# PIR_Sensor_driver_v5_1-Cheburan.net
KiCad netlist of a schematic drawn in Altium Designer
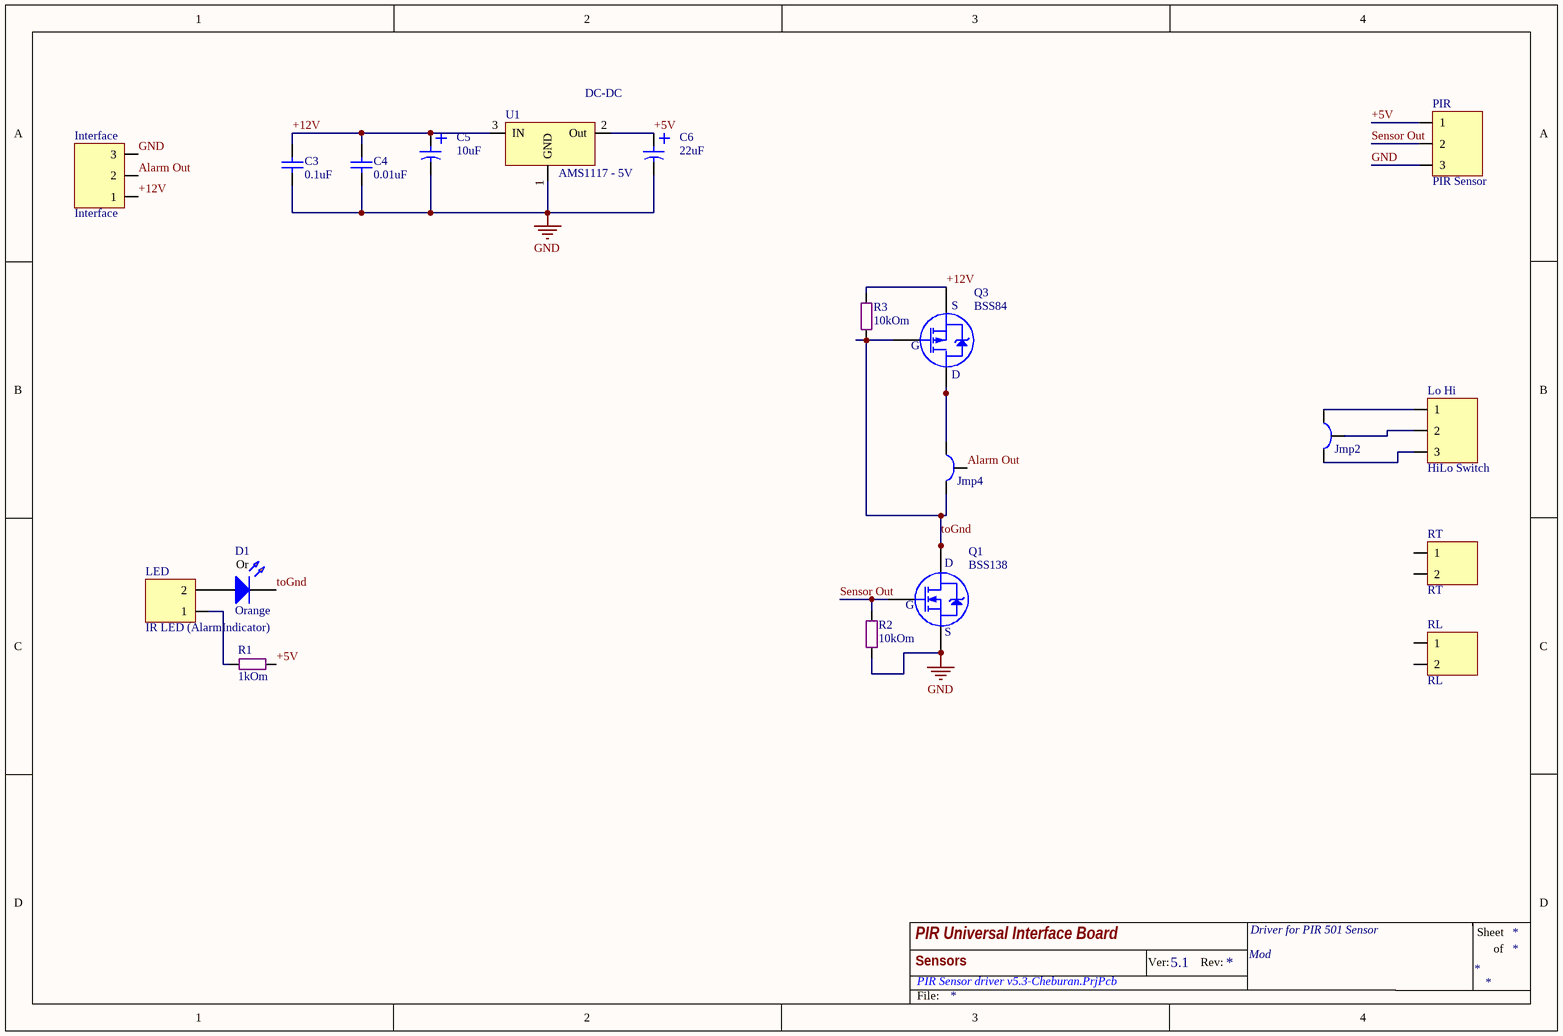
[diagram p0: PIR Sensor driver v5.1-Cheburan.SchDoc]

(export (version "E")
  (design (tool "Eeschema 10.0.6"))
  (components
    (comp (ref "C3")
      (value "0.1uF")
      (footprint "Capacitor:SMD 0805 (2012)")
      (description "Capacitor")
      (libsource (lib "Capacitor") (part "Cap SMD 0402-1812"))
    )
    (comp (ref "C4")
      (value "0.01uF")
      (footprint "Capacitor:SMD 0805 (2012)")
      (description "Capacitor")
      (libsource (lib "Capacitor") (part "Cap SMD 0402-1812"))
    )
    (comp (ref "C5")
      (value "10uF")
      (footprint "Capacitor:SMD 1206 Tantal (3216)")
      (description "Capacitor")
      (libsource (lib "Capacitor") (part "Cap Tantal"))
    )
    (comp (ref "C6")
      (value "22uF")
      (footprint "Capacitor:SMD 3528 Tantal (1210)")
      (description "Capacitor")
      (libsource (lib "Capacitor") (part "Cap Tantal"))
    )
    (comp (ref "D1")
      (value "Orange")
      (footprint "LED:LED SMD 1206-0805 Orange")
      (description "?2v ?20mA")
      (libsource (lib "LED") (part "Led SMD Orange"))
    )
    (comp (ref "Interface")
      (value "Interface")
      (footprint "Connector:Line 2.54 X 3")
      (description "Vert, Sgl line, Male")
      (libsource (lib "") (part "PLS-3_1"))
    )
    (comp (ref "Jmp2")
      (value "Jumper_3pos")
      (footprint "Jumper 3pos ws Holes")
      (libsource (lib "PassiveComponents") (part "Jumper_3pos"))
    )
    (comp (ref "Jmp4")
      (value "Jumper_3pos")
      (footprint "Jumper 3pos ws Holes")
      (libsource (lib "PassiveComponents") (part "Jumper_3pos"))
    )
    (comp (ref "LED")
      (value "IR LED (AlarmIndicator)")
      (footprint "Connector:Line 2.54 x 2")
      (description "Vert, Sgl line, Male")
      (libsource (lib "") (part "PLS-2_1"))
    )
    (comp (ref "Lo Hi")
      (value "HiLo Switch")
      (footprint "Connector:Line 2.54 X 3")
      (description "Vert, Sgl line, Male")
      (libsource (lib "Connector") (part "PLS-3"))
    )
    (comp (ref "PIR")
      (value "PIR Sensor")
      (footprint "Connector:Line 2.54 X 3")
      (description "Vert, Sgl line, Male")
      (libsource (lib "Connector") (part "PLS-3"))
    )
    (comp (ref "Q1")
      (value "BSS138")
      (footprint "GeneralCases:SOT-23")
      (description "N-Channel 50V - 0.7-1Ω - 0.22A")
      (libsource (lib "Transistor") (part "BSS138"))
    )
    (comp (ref "Q3")
      (value "BSS84")
      (footprint "GeneralCases:SOT-23")
      (description "P-Channel -50V - 10-1Ω - 0.13A")
      (libsource (lib "Transistor") (part "BSS84"))
    )
    (comp (ref "R1")
      (value "1kOm")
      (footprint "PassiveComponents:SMD 0805 (2012)")
      (libsource (lib "PassiveComponents") (part "Res All Types"))
    )
    (comp (ref "R2")
      (value "10kOm")
      (footprint "PassiveComponents:SMD 0805 (2012)")
      (libsource (lib "PassiveComponents") (part "Res All Types"))
    )
    (comp (ref "R3")
      (value "10kOm")
      (footprint "PassiveComponents:SMD 0805 (2012)")
      (libsource (lib "PassiveComponents") (part "Res All Types"))
    )
    (comp (ref "RL")
      (value "RL")
      (footprint "Connector:Line 2.54 x 2")
      (description "Vert, Sgl line, Male")
      (libsource (lib "Connector") (part "PLS-2"))
    )
    (comp (ref "RT")
      (value "RT")
      (footprint "Connector:Line 2.54 x 2")
      (description "Vert, Sgl line, Male")
      (libsource (lib "Connector") (part "PLS-2"))
    )
    (comp (ref "U1")
      (value "AMS1117 - 5V")
      (footprint "GeneralCases:SOT-223-3 (AMS)")
      (description "Voltage Regulator SOT-223-3")
      (libsource (lib "PowerAdjusment") (part "AMS1117_FIX"))
    )
  )
  (nets
    (net (code "1") (name "/+5V") (class "Default")
      (node (ref "C6") (pin "VCC") (pinfunction "1_VCC") (pintype "passive"))
      (node (ref "PIR") (pin "1") (pinfunction "1_1") (pintype "passive"))
      (node (ref "R1") (pin "1") (pinfunction "1_1") (pintype "passive"))
      (node (ref "U1") (pin "2") (pinfunction "Out_2") (pintype "power_in"))
    )
    (net (code "2") (name "/+12V") (class "Default")
      (node (ref "C3") (pin "1") (pinfunction "1_1") (pintype "passive"))
      (node (ref "C4") (pin "1") (pinfunction "1_1") (pintype "passive"))
      (node (ref "C5") (pin "VCC") (pinfunction "1_VCC") (pintype "passive"))
      (node (ref "Interface") (pin "1") (pinfunction "1_1") (pintype "passive"))
      (node (ref "Q3") (pin "2") (pinfunction "S_2") (pintype "passive"))
      (node (ref "R3") (pin "2") (pinfunction "2_2") (pintype "passive"))
      (node (ref "U1") (pin "3") (pinfunction "IN_3") (pintype "power_in"))
    )
    (net (code "3") (name "/Alarm Out") (class "Default")
      (node (ref "Interface") (pin "2") (pinfunction "2_2") (pintype "passive"))
      (node (ref "Jmp4") (pin "2") (pinfunction "2_2") (pintype "passive"))
    )
    (net (code "4") (name "/Sensor Out") (class "Default")
      (node (ref "PIR") (pin "2") (pinfunction "2_2") (pintype "passive"))
      (node (ref "Q1") (pin "1") (pinfunction "G_1") (pintype "passive"))
      (node (ref "R2") (pin "2") (pinfunction "2_2") (pintype "passive"))
    )
    (net (code "5") (name "/toGnd") (class "Default")
      (node (ref "D1") (pin "K") (pinfunction "K_K") (pintype "passive"))
      (node (ref "Jmp4") (pin "3") (pinfunction "3_3") (pintype "passive"))
      (node (ref "Q1") (pin "3") (pinfunction "D_3") (pintype "passive"))
      (node (ref "Q3") (pin "1") (pinfunction "G_1") (pintype "passive"))
      (node (ref "R3") (pin "1") (pinfunction "1_1") (pintype "passive"))
    )
    (net (code "6") (name "GND") (class "Default")
      (node (ref "C3") (pin "2") (pinfunction "2_2") (pintype "passive"))
      (node (ref "C4") (pin "2") (pinfunction "2_2") (pintype "passive"))
      (node (ref "C5") (pin "GND") (pinfunction "2_GND") (pintype "passive"))
      (node (ref "C6") (pin "GND") (pinfunction "2_GND") (pintype "passive"))
      (node (ref "Interface") (pin "3") (pinfunction "3_3") (pintype "passive"))
      (node (ref "PIR") (pin "3") (pinfunction "3_3") (pintype "passive"))
      (node (ref "Q1") (pin "2") (pinfunction "S_2") (pintype "passive"))
      (node (ref "R2") (pin "1") (pinfunction "1_1") (pintype "passive"))
      (node (ref "U1") (pin "1") (pinfunction "GND_1") (pintype "passive"))
    )
    (net (code "7") (name "Net-(D1-PadA)") (class "Default")
      (node (ref "D1") (pin "A") (pinfunction "A_A") (pintype "passive"))
      (node (ref "LED") (pin "2") (pinfunction "2_2") (pintype "passive"))
    )
    (net (code "8") (name "Net-(Jmp2-Pad1)") (class "Default")
      (node (ref "Jmp2") (pin "1") (pinfunction "1_1") (pintype "passive"))
      (node (ref "Lo Hi") (pin "1") (pinfunction "1_1") (pintype "passive"))
    )
    (net (code "9") (name "Net-(Jmp2-Pad2)") (class "Default")
      (node (ref "Jmp2") (pin "2") (pinfunction "2_2") (pintype "passive"))
      (node (ref "Lo Hi") (pin "2") (pinfunction "2_2") (pintype "passive"))
    )
    (net (code "10") (name "Net-(Jmp2-Pad3)") (class "Default")
      (node (ref "Jmp2") (pin "3") (pinfunction "3_3") (pintype "passive"))
      (node (ref "Lo Hi") (pin "3") (pinfunction "3_3") (pintype "passive"))
    )
    (net (code "11") (name "Net-(LED-Pad1)") (class "Default")
      (node (ref "LED") (pin "1") (pinfunction "1_1") (pintype "passive"))
      (node (ref "R1") (pin "2") (pinfunction "2_2") (pintype "passive"))
    )
    (net (code "12") (name "Net-(Q3-D)") (class "Default")
      (node (ref "Jmp4") (pin "1") (pinfunction "1_1") (pintype "passive"))
      (node (ref "Q3") (pin "3") (pinfunction "D_3") (pintype "passive"))
    )
    (net (code "13") (name "unconnected-(RL-Pad1)") (class "Default")
      (node (ref "RL") (pin "1") (pinfunction "1_1") (pintype "passive"))
    )
    (net (code "14") (name "unconnected-(RL-Pad2)") (class "Default")
      (node (ref "RL") (pin "2") (pinfunction "2_2") (pintype "passive"))
    )
    (net (code "15") (name "unconnected-(RT-Pad1)") (class "Default")
      (node (ref "RT") (pin "1") (pinfunction "1_1") (pintype "passive"))
    )
    (net (code "16") (name "unconnected-(RT-Pad2)") (class "Default")
      (node (ref "RT") (pin "2") (pinfunction "2_2") (pintype "passive"))
    )
  )
)
